# 2019-10-29_14-21-201.net
KiCad netlist of a schematic drawn in Altium Designer
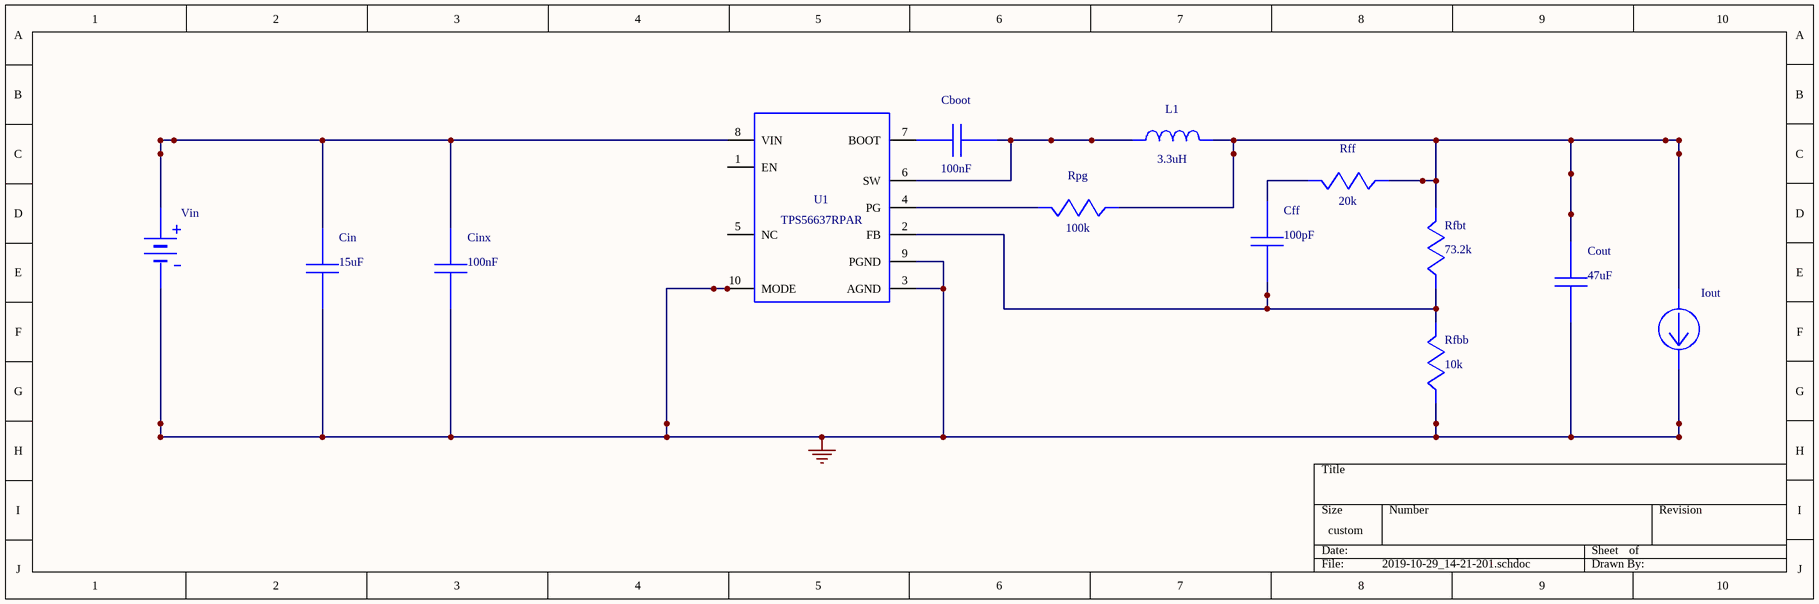
[diagram p0: 2019-10-29_14-21-201.schdoc]

(export (version "E")
  (design (tool "Eeschema 10.0.6"))
  (components
    (comp (ref "Cboot")
      (value "100nF")
      (description "C0805C104M5RACTU")
      (libsource (lib "TI WEBENCH") (part "Cboot"))
    )
    (comp (ref "Cff")
      (value "100pF")
      (description "GQM2195C1H101JB0")
      (fields (field (name "MANUFACTURER PART NUMBER") "GQM2195C1H101JB01D"))
      (libsource (lib "TI WEBENCH") (part "Cff"))
    )
    (comp (ref "Cin")
      (value "15uF")
      (description "C2012X5R1V156M12")
      (fields (field (name "MANUFACTURER PART NUMBER") "C2012X5R1V156M125AC"))
      (libsource (lib "TI WEBENCH") (part "Cin"))
    )
    (comp (ref "Cinx")
      (value "100nF")
      (description "GRM21BR71H104KA0")
      (fields (field (name "MANUFACTURER PART NUMBER") "GRM21BR71H104KA01L"))
      (libsource (lib "TI WEBENCH") (part "Cinx"))
    )
    (comp (ref "Cout")
      (value "47uF")
      (description "GRM31CR61A476KE1")
      (fields (field (name "MANUFACTURER PART NUMBER") "GRM31CR61A476KE15L"))
      (libsource (lib "TI WEBENCH") (part "Cout"))
    )
    (comp (ref "Iout") (value "WB_CURRENT_LOAD") (libsource (lib "TI WEBENCH") (part "Iout")))
    (comp (ref "L1")
      (value "3.3uH")
      (description "Unknown")
      (fields (field (name "MANUFACTURER PART NUMBER") "IHLP3232DZER3R3M01"))
      (libsource (lib "TI WEBENCH") (part "L1"))
    )
    (comp (ref "Rfbb")
      (value "10k")
      (description "CRCW080510K0FKEA")
      (libsource (lib "TI WEBENCH") (part "Rfbb"))
    )
    (comp (ref "Rfbt")
      (value "73.2k")
      (description "CRCW080573K2FKEA")
      (libsource (lib "TI WEBENCH") (part "Rfbt"))
    )
    (comp (ref "Rff")
      (value "20k")
      (description "CRCW080520K0FKEA")
      (libsource (lib "TI WEBENCH") (part "Rff"))
    )
    (comp (ref "Rpg")
      (value "100k")
      (description "CRCW0805100KFKEA")
      (libsource (lib "TI WEBENCH") (part "Rpg"))
    )
    (comp (ref "U1")
      (value "TPS56637RPAR")
      (fields (field (name "PACKAGEREFERENCE") "TPS56637RPAR"))
      (libsource (lib "TI WEBENCH") (part "U1"))
    )
    (comp (ref "Vin") (value "WB_BATTERY") (libsource (lib "TI WEBENCH") (part "Vin")))
  )
  (nets
    (net (code "1") (name "0") (class "Default")
      (node (ref "Cin") (pin "2") (pinfunction "2_2") (pintype "passive"))
      (node (ref "Cinx") (pin "2") (pinfunction "2_2") (pintype "passive"))
      (node (ref "Cout") (pin "2") (pinfunction "2_2") (pintype "passive"))
      (node (ref "Iout") (pin "2") (pinfunction "-_2") (pintype "passive"))
      (node (ref "Rfbb") (pin "2") (pinfunction "2_2") (pintype "passive"))
      (node (ref "U1") (pin "10") (pinfunction "MODE_10") (pintype "power_in"))
      (node (ref "U1") (pin "3") (pinfunction "AGND_3") (pintype "power_in"))
      (node (ref "U1") (pin "9") (pinfunction "PGND_9") (pintype "power_in"))
      (node (ref "Vin") (pin "2") (pinfunction "-_2") (pintype "passive"))
    )
    (net (code "2") (name "Net-(Cff-Pad1)") (class "Default")
      (node (ref "Cff") (pin "1") (pinfunction "1_1") (pintype "passive"))
      (node (ref "Rff") (pin "1") (pinfunction "1_1") (pintype "passive"))
    )
    (net (code "3") (name "Net-(Iout-+)") (class "Default")
      (node (ref "Cout") (pin "1") (pinfunction "1_1") (pintype "passive"))
      (node (ref "Iout") (pin "1") (pinfunction "+_1") (pintype "passive"))
      (node (ref "L1") (pin "2") (pinfunction "2_2") (pintype "passive"))
      (node (ref "Rfbt") (pin "1") (pinfunction "1_1") (pintype "passive"))
      (node (ref "Rff") (pin "2") (pinfunction "2_2") (pintype "passive"))
      (node (ref "Rpg") (pin "2") (pinfunction "2_2") (pintype "passive"))
    )
    (net (code "4") (name "Net-(U1-BOOT)") (class "Default")
      (node (ref "Cboot") (pin "1") (pinfunction "1_1") (pintype "passive"))
      (node (ref "U1") (pin "7") (pinfunction "BOOT_7") (pintype "power_in"))
    )
    (net (code "5") (name "Net-(U1-FB)") (class "Default")
      (node (ref "Cff") (pin "2") (pinfunction "2_2") (pintype "passive"))
      (node (ref "Rfbb") (pin "1") (pinfunction "1_1") (pintype "passive"))
      (node (ref "Rfbt") (pin "2") (pinfunction "2_2") (pintype "passive"))
      (node (ref "U1") (pin "2") (pinfunction "FB_2") (pintype "power_in"))
    )
    (net (code "6") (name "Net-(U1-PG)") (class "Default")
      (node (ref "Rpg") (pin "1") (pinfunction "1_1") (pintype "passive"))
      (node (ref "U1") (pin "4") (pinfunction "PG_4") (pintype "power_in"))
    )
    (net (code "7") (name "Net-(U1-SW)") (class "Default")
      (node (ref "Cboot") (pin "2") (pinfunction "2_2") (pintype "passive"))
      (node (ref "L1") (pin "1") (pinfunction "1_1") (pintype "passive"))
      (node (ref "U1") (pin "6") (pinfunction "SW_6") (pintype "power_in"))
    )
    (net (code "8") (name "Net-(U1-VIN)") (class "Default")
      (node (ref "Cin") (pin "1") (pinfunction "1_1") (pintype "passive"))
      (node (ref "Cinx") (pin "1") (pinfunction "1_1") (pintype "passive"))
      (node (ref "U1") (pin "8") (pinfunction "VIN_8") (pintype "power_in"))
      (node (ref "Vin") (pin "1") (pinfunction "+_1") (pintype "passive"))
    )
    (net (code "9") (name "unconnected-(U1-EN-Pad1)") (class "Default")
      (node (ref "U1") (pin "1") (pinfunction "EN_1") (pintype "power_in"))
    )
    (net (code "10") (name "unconnected-(U1-NC-Pad5)") (class "Default")
      (node (ref "U1") (pin "5") (pinfunction "NC_5") (pintype "passive"))
    )
  )
)
